# 1-WireDualCounter.net
KiCad netlist of a schematic drawn in EAGLE
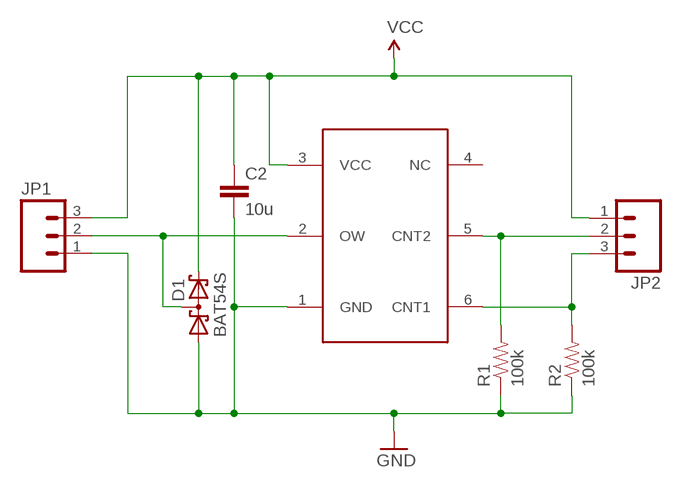
[diagram p0: schematic, sheet 1]

(export (version "E")
  (design (tool "Eeschema 10.0.6"))
  (components
    (comp (ref "C2")
      (value "10u")
      (footprint "eagle-import:0603-CAP")
      (libsource (lib "eagle-import") (part "CAP0603-CAP"))
    )
    (comp (ref "D1")
      (value "BAT54S")
      (footprint "eagle-import:SOT23")
      (libsource (lib "eagle-import") (part "BAT54S"))
    )
    (comp (ref "JP1")
      (value "M03LOCK")
      (footprint "eagle-import:1X03_LOCK")
      (libsource (lib "eagle-import") (part "M03LOCK"))
    )
    (comp (ref "JP2")
      (value "M03LOCK")
      (footprint "eagle-import:1X03_LOCK")
      (libsource (lib "eagle-import") (part "M03LOCK"))
    )
    (comp (ref "R1")
      (value "100k")
      (footprint "eagle-import:0603-RES")
      (libsource (lib "eagle-import") (part "RESISTOR0603-RES"))
    )
    (comp (ref "R2")
      (value "100k")
      (footprint "eagle-import:0603-RES")
      (libsource (lib "eagle-import") (part "RESISTOR0603-RES"))
    )
    (comp (ref "U$2")
      (value "DS2423P")
      (footprint "eagle-import:TSOC6")
      (libsource (lib "eagle-import") (part "DS2423P"))
    )
  )
  (nets
    (net (code "1") (name "GND") (class "Default")
      (node (ref "C2") (pin "2") (pinfunction "2_2") (pintype "passive"))
      (node (ref "D1") (pin "1") (pinfunction "A1_1") (pintype "passive"))
      (node (ref "JP1") (pin "1") (pinfunction "1_1") (pintype "passive"))
      (node (ref "R1") (pin "1") (pinfunction "1_1") (pintype "passive"))
      (node (ref "R2") (pin "1") (pinfunction "1_1") (pintype "passive"))
      (node (ref "U$2") (pin "1") (pinfunction "GND_1") (pintype "bidirectional"))
    )
    (net (code "2") (name "Net-(D1-C1A2)") (class "Default")
      (node (ref "D1") (pin "3") (pinfunction "C1A2_3") (pintype "passive"))
      (node (ref "JP1") (pin "2") (pinfunction "2_2") (pintype "passive"))
      (node (ref "U$2") (pin "2") (pinfunction "OW_2") (pintype "bidirectional"))
    )
    (net (code "3") (name "Net-(U$2-CNT1)") (class "Default")
      (node (ref "JP2") (pin "3") (pinfunction "3_3") (pintype "passive"))
      (node (ref "R2") (pin "2") (pinfunction "2_2") (pintype "passive"))
      (node (ref "U$2") (pin "6") (pinfunction "CNT1_6") (pintype "bidirectional"))
    )
    (net (code "4") (name "Net-(U$2-CNT2)") (class "Default")
      (node (ref "JP2") (pin "2") (pinfunction "2_2") (pintype "passive"))
      (node (ref "R1") (pin "2") (pinfunction "2_2") (pintype "passive"))
      (node (ref "U$2") (pin "5") (pinfunction "CNT2_5") (pintype "bidirectional"))
    )
    (net (code "5") (name "VCC") (class "Default")
      (node (ref "C2") (pin "1") (pinfunction "1_1") (pintype "passive"))
      (node (ref "D1") (pin "2") (pinfunction "C2_2") (pintype "passive"))
      (node (ref "JP1") (pin "3") (pinfunction "3_3") (pintype "passive"))
      (node (ref "JP2") (pin "1") (pinfunction "1_1") (pintype "passive"))
      (node (ref "U$2") (pin "3") (pinfunction "VCC_3") (pintype "bidirectional"))
    )
    (net (code "6") (name "unconnected-(U$2-NC-Pad4)") (class "Default")
      (node (ref "U$2") (pin "4") (pinfunction "NC_4") (pintype "bidirectional"))
    )
  )
)
